# AltitudeHeadingReminder.net
KiCad netlist of a schematic drawn in EasyEDA
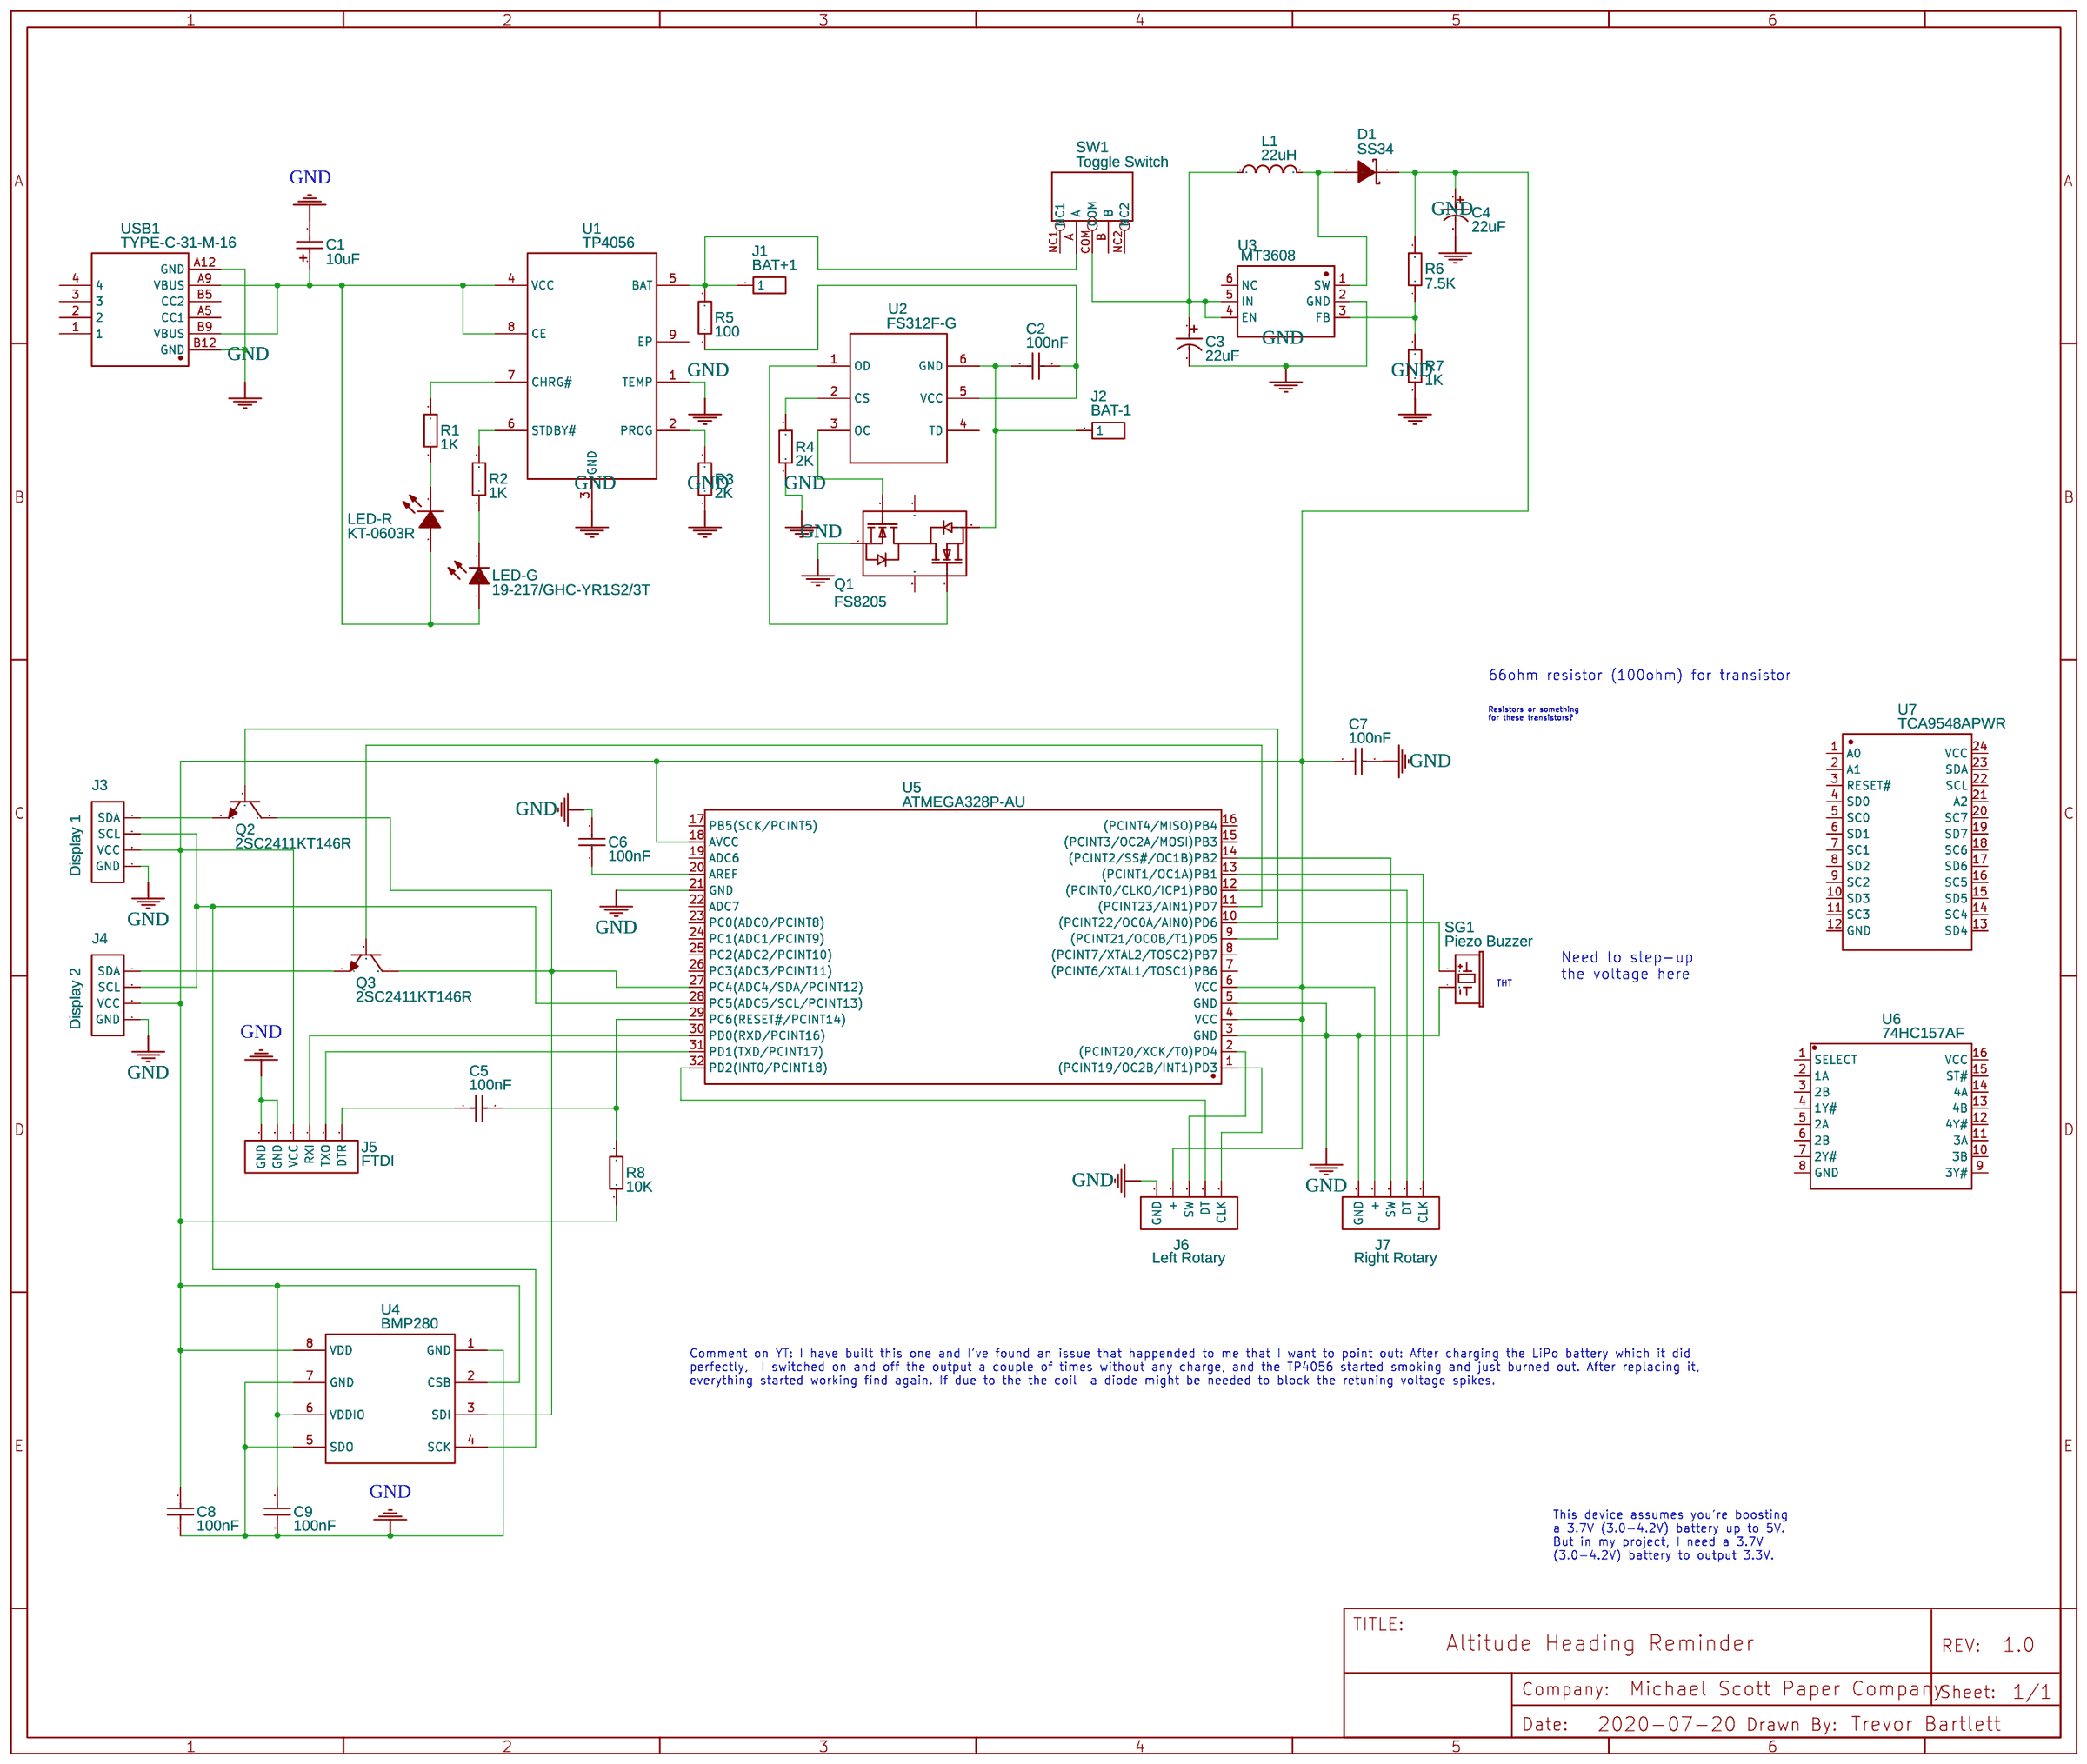
[diagram p0: schematic sheet]

(export (version "E")
  (design (tool "Eeschema 10.0.6"))
  (components
    (comp (ref "C1")
      (value "10uF")
      (fields
        (field (name "BOM_Manufacturer Part") "TAJA106K016RNJ")
        (field (name "BOM_Supplier Part") "C7171")
      )
      (libsource (lib "") (part "TAJA106K016RNJ"))
    )
    (comp (ref "C2")
      (value "100nF")
      (fields
        (field (name "BOM_Manufacturer Part") "CL05B104KO5NNNC")
        (field (name "BOM_Supplier Part") "C1525")
      )
      (libsource (lib "") (part "CL05B104KO5NNNC_3"))
    )
    (comp (ref "C3")
      (value "22uF")
      (fields
        (field (name "BOM_Manufacturer Part") "CA45-A-6.3V-22uF-M")
        (field (name "BOM_Supplier Part") "C140378")
      )
      (libsource (lib "") (part "CA45-A-6.3V-22uF-M"))
    )
    (comp (ref "C4")
      (value "22uF")
      (fields
        (field (name "BOM_Manufacturer Part") "CA45-A-6.3V-22uF-M")
        (field (name "BOM_Supplier Part") "C140378")
      )
      (libsource (lib "") (part "CA45-A-6.3V-22uF-M"))
    )
    (comp (ref "C5")
      (value "100nF")
      (fields
        (field (name "BOM_Manufacturer Part") "CL05B104KO5NNNC")
        (field (name "BOM_Supplier Part") "C1525")
      )
      (libsource (lib "") (part "CL05B104KO5NNNC_3"))
    )
    (comp (ref "C6")
      (value "100nF")
      (fields
        (field (name "BOM_Manufacturer Part") "CL05B104KO5NNNC")
        (field (name "BOM_Supplier Part") "C1525")
      )
      (libsource (lib "") (part "CL05B104KO5NNNC_1"))
    )
    (comp (ref "C7")
      (value "100nF")
      (fields
        (field (name "BOM_Manufacturer Part") "CL05B104KO5NNNC")
        (field (name "BOM_Supplier Part") "C1525")
      )
      (libsource (lib "") (part "CL05B104KO5NNNC_2"))
    )
    (comp (ref "C8")
      (value "100nF")
      (fields
        (field (name "BOM_Manufacturer Part") "CL05B104KO5NNNC")
        (field (name "BOM_Supplier Part") "C1525")
      )
      (libsource (lib "") (part "CL05B104KO5NNNC"))
    )
    (comp (ref "C9")
      (value "100nF")
      (fields
        (field (name "BOM_Manufacturer Part") "CL05B104KO5NNNC")
        (field (name "BOM_Supplier Part") "C1525")
      )
      (libsource (lib "") (part "CL05B104KO5NNNC"))
    )
    (comp (ref "D1")
      (value "SS34")
      (fields (field (name "BOM_Supplier Part") "C8678"))
      (libsource (lib "") (part "Unknown_830_-1235"))
    )
    (comp (ref "J1")
      (value "BAT+1")
      (fields (field (name "BOM_Supplier Part") "C81276"))
      (libsource (lib "") (part "HDR-M-2.54_1x1"))
    )
    (comp (ref "J2")
      (value "BAT-1")
      (fields (field (name "BOM_Supplier Part") "C81276"))
      (libsource (lib "") (part "HDR-M-2.54_1x1"))
    )
    (comp (ref "J3")
      (value "Display 1")
      (fields (field (name "BOM_Supplier Part") "C124378"))
      (libsource (lib "") (part "HDR-M-2.54_1x4"))
    )
    (comp (ref "J4")
      (value "Display 2")
      (fields (field (name "BOM_Supplier Part") "C124378"))
      (libsource (lib "") (part "HDR-M-2.54_1x4"))
    )
    (comp (ref "J5")
      (value "FTDI")
      (fields (field (name "BOM_Supplier Part") "C190819"))
      (libsource (lib "") (part "HDR-M-2.54_1x6"))
    )
    (comp (ref "J6")
      (value "Left Rotary")
      (fields (field (name "BOM_Supplier Part") "C358687"))
      (libsource (lib "") (part "HDR-M-2.54_1x5"))
    )
    (comp (ref "J7")
      (value "Right Rotary")
      (fields (field (name "BOM_Supplier Part") "C358687"))
      (libsource (lib "") (part "HDR-M-2.54_1x5"))
    )
    (comp (ref "L1")
      (value "22uH")
      (fields
        (field (name "BOM_Manufacturer Part") "SDFL2012T220KTF")
        (field (name "BOM_Supplier Part") "C32375")
      )
      (libsource (lib "") (part "SDFL2012T220KTF"))
    )
    (comp (ref "LED-G")
      (value "19-217/GHC-YR1S2/3T")
      (fields (field (name "BOM_Supplier Part") "C72043"))
      (libsource (lib "") (part "19-217/GHC-YR1S2/3T"))
    )
    (comp (ref "LED-R")
      (value "KT-0603R")
      (fields (field (name "BOM_Supplier Part") "C2286"))
      (libsource (lib "") (part "KT-0603R"))
    )
    (comp (ref "Q1")
      (value "FS8205")
      (fields (field (name "BOM_Supplier Part") "C32254"))
      (libsource (lib "") (part "Unknown_550_-1005"))
    )
    (comp (ref "Q2")
      (value "2SC2411KT146R")
      (fields (field (name "BOM_Supplier Part") "C122622"))
      (libsource (lib "") (part "2SC2411KT146R"))
    )
    (comp (ref "Q3")
      (value "2SC2411KT146R")
      (fields (field (name "BOM_Supplier Part") "C122622"))
      (libsource (lib "") (part "2SC2411KT146R"))
    )
    (comp (ref "R1")
      (value "1K")
      (fields
        (field (name "BOM_Manufacturer Part") "0402WGF1001TCE")
        (field (name "BOM_Supplier Part") "C11702")
      )
      (libsource (lib "") (part "0402WGF1001TCE"))
    )
    (comp (ref "R2")
      (value "1K")
      (fields
        (field (name "BOM_Manufacturer Part") "0402WGF1001TCE")
        (field (name "BOM_Supplier Part") "C11702")
      )
      (libsource (lib "") (part "0402WGF1001TCE"))
    )
    (comp (ref "R3")
      (value "2K")
      (fields
        (field (name "BOM_Manufacturer Part") "0402WGF2001TCE")
        (field (name "BOM_Supplier Part") "C4109")
      )
      (libsource (lib "") (part "0402WGF2001TCE"))
    )
    (comp (ref "R4")
      (value "2K")
      (fields
        (field (name "BOM_Manufacturer Part") "0402WGF2001TCE")
        (field (name "BOM_Supplier Part") "C4109")
      )
      (libsource (lib "") (part "0402WGF2001TCE"))
    )
    (comp (ref "R5")
      (value "100")
      (fields
        (field (name "BOM_Manufacturer Part") "1206W4F1000T5E")
        (field (name "BOM_Supplier Part") "C17901")
      )
      (libsource (lib "") (part "1206W4F1000T5E"))
    )
    (comp (ref "R6")
      (value "7.5K")
      (fields
        (field (name "BOM_Manufacturer Part") "AECR2010F7K50K9")
        (field (name "BOM_Supplier Part") "C351751")
      )
      (libsource (lib "") (part "AECR2010F7K50K9"))
    )
    (comp (ref "R7")
      (value "1K")
      (fields
        (field (name "BOM_Manufacturer Part") "0402WGF1001TCE")
        (field (name "BOM_Supplier Part") "C11702")
      )
      (libsource (lib "") (part "0402WGF1001TCE"))
    )
    (comp (ref "R8")
      (value "10K")
      (fields
        (field (name "BOM_Manufacturer Part") "1206W4F1002T5E")
        (field (name "BOM_Supplier Part") "C17902")
      )
      (libsource (lib "") (part "1206W4F1002T5E"))
    )
    (comp (ref "SG1") (value "Piezo Buzzer") (libsource (lib "") (part "Piezo Buzzer")))
    (comp (ref "SW1")
      (value "Toggle Switch")
      (fields (field (name "BOM_Manufacturer Part") "3P-2.0-90D-REINFORCE;"))
      (libsource (lib "") (part "Unknown_660_-1225"))
    )
    (comp (ref "U1")
      (value "TP4056")
      (fields (field (name "BOM_Supplier Part") "C16581"))
      (libsource (lib "") (part "TP4056"))
    )
    (comp (ref "U2")
      (value "FS312F-G")
      (fields (field (name "BOM_Manufacturer Part") "DW01+G") (field (name "BOM_Supplier Part") "C14213"))
      (libsource (lib "") (part "Unknown_510_-1135"))
    )
    (comp (ref "U3")
      (value "MT3608")
      (fields (field (name "BOM_Supplier Part") "C84817"))
      (libsource (lib "") (part "Unknown_790_-1175"))
    )
    (comp (ref "U4")
      (value "BMP280")
      (fields (field (name "BOM_Supplier Part") "C83291"))
      (libsource (lib "") (part "BMP280"))
    )
    (comp (ref "U5")
      (value "ATMEGA328P-AU")
      (fields (field (name "BOM_Supplier Part") "C14877"))
      (libsource (lib "") (part "ATMEGA328P-AU"))
    )
    (comp (ref "U6")
      (value "74HC157AF")
      (fields (field (name "BOM_Supplier Part") "C8166"))
      (libsource (lib "") (part "74HC157AF"))
    )
    (comp (ref "U7")
      (value "TCA9548APWR")
      (fields (field (name "BOM_Supplier Part") "C130026"))
      (libsource (lib "") (part "TCA9548APWR"))
    )
    (comp (ref "USB1")
      (value "TYPE-C-31-M-16")
      (fields (field (name "BOM_Supplier Part") "C283541"))
      (libsource (lib "") (part "TYPE-C-31-M-16"))
    )
  )
  (nets
    (net (code "1") (name "GND") (class "Default")
      (node (ref "C1") (pin "2") (pinfunction "2_2") (pintype "input"))
      (node (ref "C3") (pin "2") (pinfunction "2_2") (pintype "input"))
      (node (ref "C4") (pin "2") (pinfunction "2_2") (pintype "input"))
      (node (ref "C6") (pin "1") (pinfunction "1_1") (pintype "input"))
      (node (ref "C7") (pin "2") (pinfunction "2_2") (pintype "input"))
      (node (ref "C8") (pin "1") (pinfunction "1_1") (pintype "input"))
      (node (ref "C9") (pin "1") (pinfunction "1_1") (pintype "input"))
      (node (ref "J3") (pin "1") (pinfunction "GND_1") (pintype "unspecified"))
      (node (ref "J4") (pin "1") (pinfunction "GND_1") (pintype "unspecified"))
      (node (ref "J5") (pin "5") (pinfunction "GND_5") (pintype "unspecified"))
      (node (ref "J5") (pin "6") (pinfunction "GND_6") (pintype "unspecified"))
      (node (ref "J6") (pin "5") (pinfunction "GND_5") (pintype "unspecified"))
      (node (ref "J7") (pin "5") (pinfunction "GND_5") (pintype "unspecified"))
      (node (ref "Q1") (pin "1") (pinfunction "S1_1") (pintype "unspecified"))
      (node (ref "R3") (pin "1") (pinfunction "1_1") (pintype "input"))
      (node (ref "R4") (pin "1") (pinfunction "1_1") (pintype "input"))
      (node (ref "R7") (pin "1") (pinfunction "1_1") (pintype "input"))
      (node (ref "SG1") (pin "-") (pinfunction "2_-") (pintype "unspecified"))
      (node (ref "U1") (pin "1") (pinfunction "TEMP_1") (pintype "unspecified"))
      (node (ref "U1") (pin "3") (pinfunction "GND_3") (pintype "unspecified"))
      (node (ref "U3") (pin "2") (pinfunction "GND_2") (pintype "unspecified"))
      (node (ref "U4") (pin "1") (pinfunction "GND_1") (pintype "unspecified"))
      (node (ref "U4") (pin "5") (pinfunction "SDO_5") (pintype "unspecified"))
      (node (ref "U4") (pin "7") (pinfunction "GND_7") (pintype "unspecified"))
      (node (ref "U5") (pin "21") (pinfunction "GND_21") (pintype "unspecified"))
      (node (ref "U5") (pin "3") (pinfunction "GND_3") (pintype "unspecified"))
      (node (ref "U5") (pin "5") (pinfunction "GND_5") (pintype "unspecified"))
      (node (ref "USB1") (pin "A12") (pinfunction "GND_A12") (pintype "unspecified"))
      (node (ref "USB1") (pin "B12") (pinfunction "GND_B12") (pintype "unspecified"))
    )
    (net (code "2") (name "Net-(D1-A)") (class "Default")
      (node (ref "D1") (pin "1") (pinfunction "A_1") (pintype "unspecified"))
      (node (ref "L1") (pin "2") (pinfunction "2_2") (pintype "unspecified"))
      (node (ref "U3") (pin "1") (pinfunction "SW_1") (pintype "unspecified"))
    )
    (net (code "3") (name "Net-(D1-K)") (class "Default")
      (node (ref "C4") (pin "1") (pinfunction "1_1") (pintype "input"))
      (node (ref "C7") (pin "1") (pinfunction "1_1") (pintype "input"))
      (node (ref "C8") (pin "2") (pinfunction "2_2") (pintype "input"))
      (node (ref "C9") (pin "2") (pinfunction "2_2") (pintype "input"))
      (node (ref "D1") (pin "2") (pinfunction "K_2") (pintype "unspecified"))
      (node (ref "J3") (pin "2") (pinfunction "VCC_2") (pintype "unspecified"))
      (node (ref "J4") (pin "2") (pinfunction "VCC_2") (pintype "unspecified"))
      (node (ref "J5") (pin "4") (pinfunction "VCC_4") (pintype "passive"))
      (node (ref "J6") (pin "4") (pinfunction "+_4") (pintype "unspecified"))
      (node (ref "J7") (pin "4") (pinfunction "+_4") (pintype "unspecified"))
      (node (ref "R6") (pin "2") (pinfunction "2_2") (pintype "unspecified"))
      (node (ref "R8") (pin "1") (pinfunction "1_1") (pintype "input"))
      (node (ref "U4") (pin "2") (pinfunction "CSB_2") (pintype "unspecified"))
      (node (ref "U4") (pin "6") (pinfunction "VDDIO_6") (pintype "unspecified"))
      (node (ref "U4") (pin "8") (pinfunction "VDD_8") (pintype "unspecified"))
      (node (ref "U5") (pin "18") (pinfunction "AVCC_18") (pintype "unspecified"))
      (node (ref "U5") (pin "4") (pinfunction "VCC_4") (pintype "unspecified"))
      (node (ref "U5") (pin "6") (pinfunction "VCC_6") (pintype "unspecified"))
    )
    (net (code "4") (name "Net-(J3-SCL)") (class "Default")
      (node (ref "J3") (pin "3") (pinfunction "SCL_3") (pintype "unspecified"))
      (node (ref "J4") (pin "3") (pinfunction "SCL_3") (pintype "unspecified"))
      (node (ref "U4") (pin "4") (pinfunction "SCK_4") (pintype "unspecified"))
      (node (ref "U5") (pin "28") (pinfunction "PC5(ADC5/SCL/PCINT13)_28") (pintype "unspecified"))
    )
    (net (code "5") (name "Net-(J3-SDA)") (class "Default")
      (node (ref "J3") (pin "4") (pinfunction "SDA_4") (pintype "unspecified"))
      (node (ref "Q2") (pin "1") (pinfunction "E_1") (pintype "unspecified"))
    )
    (net (code "6") (name "Net-(J4-SDA)") (class "Default")
      (node (ref "J4") (pin "4") (pinfunction "SDA_4") (pintype "unspecified"))
      (node (ref "Q3") (pin "1") (pinfunction "E_1") (pintype "unspecified"))
    )
    (net (code "7") (name "Net-(J5-DTR)") (class "Default")
      (node (ref "C5") (pin "2") (pinfunction "2_2") (pintype "input"))
      (node (ref "J5") (pin "1") (pinfunction "DTR_1") (pintype "unspecified"))
    )
    (net (code "8") (name "Net-(J5-RXI)") (class "Default")
      (node (ref "J5") (pin "3") (pinfunction "RXI_3") (pintype "unspecified"))
      (node (ref "U5") (pin "30") (pinfunction "PD0(RXD/PCINT16)_30") (pintype "unspecified"))
    )
    (net (code "9") (name "Net-(J5-TXO)") (class "Default")
      (node (ref "J5") (pin "2") (pinfunction "TXO_2") (pintype "unspecified"))
      (node (ref "U5") (pin "31") (pinfunction "PD1(TXD/PCINT17)_31") (pintype "unspecified"))
    )
    (net (code "10") (name "Net-(J6-CLK)") (class "Default")
      (node (ref "J6") (pin "1") (pinfunction "CLK_1") (pintype "unspecified"))
      (node (ref "U5") (pin "1") (pinfunction "(PCINT19/OC2B/INT1)PD3_1") (pintype "unspecified"))
    )
    (net (code "11") (name "Net-(J6-DT)") (class "Default")
      (node (ref "J6") (pin "2") (pinfunction "DT_2") (pintype "unspecified"))
      (node (ref "U5") (pin "32") (pinfunction "PD2(INT0/PCINT18)_32") (pintype "unspecified"))
    )
    (net (code "12") (name "Net-(J6-SW)") (class "Default")
      (node (ref "J6") (pin "3") (pinfunction "SW_3") (pintype "unspecified"))
      (node (ref "U5") (pin "2") (pinfunction "(PCINT20/XCK/T0)PD4_2") (pintype "unspecified"))
    )
    (net (code "13") (name "Net-(J7-CLK)") (class "Default")
      (node (ref "J7") (pin "1") (pinfunction "CLK_1") (pintype "unspecified"))
      (node (ref "U5") (pin "13") (pinfunction "(PCINT1/OC1A)PB1_13") (pintype "unspecified"))
    )
    (net (code "14") (name "Net-(J7-DT)") (class "Default")
      (node (ref "J7") (pin "2") (pinfunction "DT_2") (pintype "unspecified"))
      (node (ref "U5") (pin "12") (pinfunction "(PCINT0/CLKO/ICP1)PB0_12") (pintype "unspecified"))
    )
    (net (code "15") (name "Net-(J7-SW)") (class "Default")
      (node (ref "J7") (pin "3") (pinfunction "SW_3") (pintype "unspecified"))
      (node (ref "U5") (pin "14") (pinfunction "(PCINT2/SS#/OC1B)PB2_14") (pintype "unspecified"))
    )
    (net (code "16") (name "Net-(LED-G-A)") (class "Default")
      (node (ref "C1") (pin "1") (pinfunction "1_1") (pintype "input"))
      (node (ref "LED-G") (pin "1") (pinfunction "A_1") (pintype "input"))
      (node (ref "LED-R") (pin "1") (pinfunction "A_1") (pintype "unspecified"))
      (node (ref "U1") (pin "4") (pinfunction "VCC_4") (pintype "unspecified"))
      (node (ref "U1") (pin "8") (pinfunction "CE_8") (pintype "unspecified"))
      (node (ref "USB1") (pin "A9") (pinfunction "VBUS_A9") (pintype "unspecified"))
      (node (ref "USB1") (pin "B9") (pinfunction "VBUS_B9") (pintype "unspecified"))
    )
    (net (code "17") (name "Net-(LED-G-C)") (class "Default")
      (node (ref "LED-G") (pin "2") (pinfunction "C_2") (pintype "input"))
      (node (ref "R2") (pin "1") (pinfunction "1_1") (pintype "input"))
    )
    (net (code "18") (name "Net-(LED-R-K)") (class "Default")
      (node (ref "LED-R") (pin "2") (pinfunction "K_2") (pintype "unspecified"))
      (node (ref "R1") (pin "1") (pinfunction "1_1") (pintype "input"))
    )
    (net (code "19") (name "Net-(Q1-G1)") (class "Default")
      (node (ref "Q1") (pin "6") (pinfunction "G1_6") (pintype "unspecified"))
      (node (ref "U2") (pin "3") (pinfunction "OC_3") (pintype "unspecified"))
    )
    (net (code "20") (name "Net-(Q1-G2)") (class "Default")
      (node (ref "Q1") (pin "4") (pinfunction "G2_4") (pintype "unspecified"))
      (node (ref "U2") (pin "1") (pinfunction "OD_1") (pintype "unspecified"))
    )
    (net (code "21") (name "Net-(Q1-S2)") (class "Default")
      (node (ref "C2") (pin "2") (pinfunction "2_2") (pintype "input"))
      (node (ref "J2") (pin "1") (pinfunction "1_1") (pintype "input"))
      (node (ref "Q1") (pin "3") (pinfunction "S2_3") (pintype "unspecified"))
      (node (ref "U2") (pin "6") (pinfunction "GND_6") (pintype "unspecified"))
    )
    (net (code "22") (name "Net-(Q2-B)") (class "Default")
      (node (ref "Q2") (pin "2") (pinfunction "B_2") (pintype "unspecified"))
      (node (ref "U5") (pin "9") (pinfunction "(PCINT21/OC0B/T1)PD5_9") (pintype "unspecified"))
    )
    (net (code "23") (name "Net-(Q2-C)") (class "Default")
      (node (ref "Q2") (pin "3") (pinfunction "C_3") (pintype "unspecified"))
      (node (ref "Q3") (pin "3") (pinfunction "C_3") (pintype "unspecified"))
      (node (ref "U4") (pin "3") (pinfunction "SDI_3") (pintype "unspecified"))
      (node (ref "U5") (pin "27") (pinfunction "PC4(ADC4/SDA/PCINT12)_27") (pintype "unspecified"))
    )
    (net (code "24") (name "Net-(Q3-B)") (class "Default")
      (node (ref "Q3") (pin "2") (pinfunction "B_2") (pintype "unspecified"))
      (node (ref "U5") (pin "11") (pinfunction "(PCINT23/AIN1)PD7_11") (pintype "unspecified"))
    )
    (net (code "25") (name "Net-(SG1-1)") (class "Default")
      (node (ref "SG1") (pin "+") (pinfunction "1_+") (pintype "unspecified"))
      (node (ref "U5") (pin "10") (pinfunction "(PCINT22/OC0A/AIN0)PD6_10") (pintype "unspecified"))
    )
    (net (code "26") (name "Net-(U1-BAT)") (class "Default")
      (node (ref "J1") (pin "1") (pinfunction "1_1") (pintype "input"))
      (node (ref "R5") (pin "2") (pinfunction "2_2") (pintype "input"))
      (node (ref "SW1") (pin "A") (pinfunction "A_A") (pintype "unspecified"))
      (node (ref "U1") (pin "5") (pinfunction "BAT_5") (pintype "unspecified"))
    )
    (net (code "27") (name "Net-(U1-CHRG#)") (class "Default")
      (node (ref "R1") (pin "2") (pinfunction "2_2") (pintype "input"))
      (node (ref "U1") (pin "7") (pinfunction "CHRG#_7") (pintype "unspecified"))
    )
    (net (code "28") (name "Net-(U1-PROG)") (class "Default")
      (node (ref "R3") (pin "2") (pinfunction "2_2") (pintype "input"))
      (node (ref "U1") (pin "2") (pinfunction "PROG_2") (pintype "unspecified"))
    )
    (net (code "29") (name "Net-(U1-STDBY#)") (class "Default")
      (node (ref "R2") (pin "2") (pinfunction "2_2") (pintype "input"))
      (node (ref "U1") (pin "6") (pinfunction "STDBY#_6") (pintype "unspecified"))
    )
    (net (code "30") (name "Net-(U2-CS)") (class "Default")
      (node (ref "R4") (pin "2") (pinfunction "2_2") (pintype "input"))
      (node (ref "U2") (pin "2") (pinfunction "CS_2") (pintype "unspecified"))
    )
    (net (code "31") (name "Net-(U2-VCC)") (class "Default")
      (node (ref "C2") (pin "1") (pinfunction "1_1") (pintype "input"))
      (node (ref "R5") (pin "1") (pinfunction "1_1") (pintype "input"))
      (node (ref "U2") (pin "5") (pinfunction "VCC_5") (pintype "unspecified"))
    )
    (net (code "32") (name "Net-(U3-EN)") (class "Default")
      (node (ref "C3") (pin "1") (pinfunction "1_1") (pintype "input"))
      (node (ref "L1") (pin "1") (pinfunction "1_1") (pintype "unspecified"))
      (node (ref "SW1") (pin "COM") (pinfunction "COM_COM") (pintype "unspecified"))
      (node (ref "U3") (pin "4") (pinfunction "EN_4") (pintype "unspecified"))
      (node (ref "U3") (pin "5") (pinfunction "IN_5") (pintype "unspecified"))
    )
    (net (code "33") (name "Net-(U3-FB)") (class "Default")
      (node (ref "R6") (pin "1") (pinfunction "1_1") (pintype "unspecified"))
      (node (ref "R7") (pin "2") (pinfunction "2_2") (pintype "input"))
      (node (ref "U3") (pin "3") (pinfunction "FB_3") (pintype "unspecified"))
    )
    (net (code "34") (name "Net-(U5-AREF)") (class "Default")
      (node (ref "C6") (pin "2") (pinfunction "2_2") (pintype "input"))
      (node (ref "U5") (pin "20") (pinfunction "AREF_20") (pintype "unspecified"))
    )
    (net (code "35") (name "Net-(U5-PC6(RESET#{slash}PCINT14))") (class "Default")
      (node (ref "C5") (pin "1") (pinfunction "1_1") (pintype "input"))
      (node (ref "R8") (pin "2") (pinfunction "2_2") (pintype "input"))
      (node (ref "U5") (pin "29") (pinfunction "PC6(RESET#/PCINT14)_29") (pintype "unspecified"))
    )
    (net (code "36") (name "unconnected-(Q1-D12-Pad2)") (class "Default")
      (node (ref "Q1") (pin "2") (pinfunction "D12_2") (pintype "unspecified"))
    )
    (net (code "37") (name "unconnected-(Q1-D12-Pad5)") (class "Default")
      (node (ref "Q1") (pin "5") (pinfunction "D12_5") (pintype "unspecified"))
    )
    (net (code "38") (name "unconnected-(SW1-PadB)") (class "Default")
      (node (ref "SW1") (pin "B") (pinfunction "B_B") (pintype "unspecified"))
    )
    (net (code "39") (name "unconnected-(SW1-PadNC1)") (class "Default")
      (node (ref "SW1") (pin "NC1") (pinfunction "NC1_NC1") (pintype "unspecified"))
    )
    (net (code "40") (name "unconnected-(SW1-PadNC2)") (class "Default")
      (node (ref "SW1") (pin "NC2") (pinfunction "NC2_NC2") (pintype "unspecified"))
    )
    (net (code "41") (name "unconnected-(U1-EP-Pad9)") (class "Default")
      (node (ref "U1") (pin "9") (pinfunction "EP_9") (pintype "unspecified"))
    )
    (net (code "42") (name "unconnected-(U2-TD-Pad4)") (class "Default")
      (node (ref "U2") (pin "4") (pinfunction "TD_4") (pintype "unspecified"))
    )
    (net (code "43") (name "unconnected-(U3-NC-Pad6)") (class "Default")
      (node (ref "U3") (pin "6") (pinfunction "NC_6") (pintype "unspecified"))
    )
    (net (code "44") (name "unconnected-(U5-(PCINT3{slash}OC2A{slash}MOSI)PB3-Pad15)") (class "Default")
      (node (ref "U5") (pin "15") (pinfunction "(PCINT3/OC2A/MOSI)PB3_15") (pintype "unspecified"))
    )
    (net (code "45") (name "unconnected-(U5-(PCINT4{slash}MISO)PB4-Pad16)") (class "Default")
      (node (ref "U5") (pin "16") (pinfunction "(PCINT4/MISO)PB4_16") (pintype "unspecified"))
    )
    (net (code "46") (name "unconnected-(U5-(PCINT6{slash}XTAL1{slash}TOSC1)PB6-Pad7)") (class "Default")
      (node (ref "U5") (pin "7") (pinfunction "(PCINT6/XTAL1/TOSC1)PB6_7") (pintype "unspecified"))
    )
    (net (code "47") (name "unconnected-(U5-(PCINT7{slash}XTAL2{slash}TOSC2)PB7-Pad8)") (class "Default")
      (node (ref "U5") (pin "8") (pinfunction "(PCINT7/XTAL2/TOSC2)PB7_8") (pintype "unspecified"))
    )
    (net (code "48") (name "unconnected-(U5-ADC6-Pad19)") (class "Default")
      (node (ref "U5") (pin "19") (pinfunction "ADC6_19") (pintype "unspecified"))
    )
    (net (code "49") (name "unconnected-(U5-ADC7-Pad22)") (class "Default")
      (node (ref "U5") (pin "22") (pinfunction "ADC7_22") (pintype "unspecified"))
    )
    (net (code "50") (name "unconnected-(U5-PB5(SCK{slash}PCINT5)-Pad17)") (class "Default")
      (node (ref "U5") (pin "17") (pinfunction "PB5(SCK/PCINT5)_17") (pintype "unspecified"))
    )
    (net (code "51") (name "unconnected-(U5-PC0(ADC0{slash}PCINT8)-Pad23)") (class "Default")
      (node (ref "U5") (pin "23") (pinfunction "PC0(ADC0/PCINT8)_23") (pintype "unspecified"))
    )
    (net (code "52") (name "unconnected-(U5-PC1(ADC1{slash}PCINT9)-Pad24)") (class "Default")
      (node (ref "U5") (pin "24") (pinfunction "PC1(ADC1/PCINT9)_24") (pintype "unspecified"))
    )
    (net (code "53") (name "unconnected-(U5-PC2(ADC2{slash}PCINT10)-Pad25)") (class "Default")
      (node (ref "U5") (pin "25") (pinfunction "PC2(ADC2/PCINT10)_25") (pintype "unspecified"))
    )
    (net (code "54") (name "unconnected-(U5-PC3(ADC3{slash}PCINT11)-Pad26)") (class "Default")
      (node (ref "U5") (pin "26") (pinfunction "PC3(ADC3/PCINT11)_26") (pintype "unspecified"))
    )
    (net (code "55") (name "unconnected-(U6-1A-Pad2)") (class "Default")
      (node (ref "U6") (pin "2") (pinfunction "1A_2") (pintype "unspecified"))
    )
    (net (code "56") (name "unconnected-(U6-1Y#-Pad4)") (class "Default")
      (node (ref "U6") (pin "4") (pinfunction "1Y#_4") (pintype "unspecified"))
    )
    (net (code "57") (name "unconnected-(U6-2A-Pad5)") (class "Default")
      (node (ref "U6") (pin "5") (pinfunction "2A_5") (pintype "unspecified"))
    )
    (net (code "58") (name "unconnected-(U6-2B-Pad3)") (class "Default")
      (node (ref "U6") (pin "3") (pinfunction "2B_3") (pintype "unspecified"))
    )
    (net (code "59") (name "unconnected-(U6-2B-Pad6)") (class "Default")
      (node (ref "U6") (pin "6") (pinfunction "2B_6") (pintype "unspecified"))
    )
    (net (code "60") (name "unconnected-(U6-2Y#-Pad7)") (class "Default")
      (node (ref "U6") (pin "7") (pinfunction "2Y#_7") (pintype "unspecified"))
    )
    (net (code "61") (name "unconnected-(U6-3A-Pad11)") (class "Default")
      (node (ref "U6") (pin "11") (pinfunction "3A_11") (pintype "unspecified"))
    )
    (net (code "62") (name "unconnected-(U6-3B-Pad10)") (class "Default")
      (node (ref "U6") (pin "10") (pinfunction "3B_10") (pintype "unspecified"))
    )
    (net (code "63") (name "unconnected-(U6-3Y#-Pad9)") (class "Default")
      (node (ref "U6") (pin "9") (pinfunction "3Y#_9") (pintype "unspecified"))
    )
    (net (code "64") (name "unconnected-(U6-4A-Pad14)") (class "Default")
      (node (ref "U6") (pin "14") (pinfunction "4A_14") (pintype "unspecified"))
    )
    (net (code "65") (name "unconnected-(U6-4B-Pad13)") (class "Default")
      (node (ref "U6") (pin "13") (pinfunction "4B_13") (pintype "unspecified"))
    )
    (net (code "66") (name "unconnected-(U6-4Y#-Pad12)") (class "Default")
      (node (ref "U6") (pin "12") (pinfunction "4Y#_12") (pintype "unspecified"))
    )
    (net (code "67") (name "unconnected-(U6-GND-Pad8)") (class "Default")
      (node (ref "U6") (pin "8") (pinfunction "GND_8") (pintype "unspecified"))
    )
    (net (code "68") (name "unconnected-(U6-SELECT-Pad1)") (class "Default")
      (node (ref "U6") (pin "1") (pinfunction "SELECT_1") (pintype "unspecified"))
    )
    (net (code "69") (name "unconnected-(U6-ST#-Pad15)") (class "Default")
      (node (ref "U6") (pin "15") (pinfunction "ST#_15") (pintype "unspecified"))
    )
    (net (code "70") (name "unconnected-(U6-VCC-Pad16)") (class "Default")
      (node (ref "U6") (pin "16") (pinfunction "VCC_16") (pintype "unspecified"))
    )
    (net (code "71") (name "unconnected-(U7-A0-Pad1)") (class "Default")
      (node (ref "U7") (pin "1") (pinfunction "A0_1") (pintype "unspecified"))
    )
    (net (code "72") (name "unconnected-(U7-A1-Pad2)") (class "Default")
      (node (ref "U7") (pin "2") (pinfunction "A1_2") (pintype "unspecified"))
    )
    (net (code "73") (name "unconnected-(U7-A2-Pad21)") (class "Default")
      (node (ref "U7") (pin "21") (pinfunction "A2_21") (pintype "unspecified"))
    )
    (net (code "74") (name "unconnected-(U7-GND-Pad12)") (class "Default")
      (node (ref "U7") (pin "12") (pinfunction "GND_12") (pintype "unspecified"))
    )
    (net (code "75") (name "unconnected-(U7-RESET#-Pad3)") (class "Default")
      (node (ref "U7") (pin "3") (pinfunction "RESET#_3") (pintype "unspecified"))
    )
    (net (code "76") (name "unconnected-(U7-SC0-Pad5)") (class "Default")
      (node (ref "U7") (pin "5") (pinfunction "SC0_5") (pintype "unspecified"))
    )
    (net (code "77") (name "unconnected-(U7-SC1-Pad7)") (class "Default")
      (node (ref "U7") (pin "7") (pinfunction "SC1_7") (pintype "unspecified"))
    )
    (net (code "78") (name "unconnected-(U7-SC2-Pad9)") (class "Default")
      (node (ref "U7") (pin "9") (pinfunction "SC2_9") (pintype "unspecified"))
    )
    (net (code "79") (name "unconnected-(U7-SC3-Pad11)") (class "Default")
      (node (ref "U7") (pin "11") (pinfunction "SC3_11") (pintype "unspecified"))
    )
    (net (code "80") (name "unconnected-(U7-SC4-Pad14)") (class "Default")
      (node (ref "U7") (pin "14") (pinfunction "SC4_14") (pintype "unspecified"))
    )
    (net (code "81") (name "unconnected-(U7-SC5-Pad16)") (class "Default")
      (node (ref "U7") (pin "16") (pinfunction "SC5_16") (pintype "unspecified"))
    )
    (net (code "82") (name "unconnected-(U7-SC6-Pad18)") (class "Default")
      (node (ref "U7") (pin "18") (pinfunction "SC6_18") (pintype "unspecified"))
    )
    (net (code "83") (name "unconnected-(U7-SC7-Pad20)") (class "Default")
      (node (ref "U7") (pin "20") (pinfunction "SC7_20") (pintype "unspecified"))
    )
    (net (code "84") (name "unconnected-(U7-SCL-Pad22)") (class "Default")
      (node (ref "U7") (pin "22") (pinfunction "SCL_22") (pintype "unspecified"))
    )
    (net (code "85") (name "unconnected-(U7-SD0-Pad4)") (class "Default")
      (node (ref "U7") (pin "4") (pinfunction "SD0_4") (pintype "unspecified"))
    )
    (net (code "86") (name "unconnected-(U7-SD1-Pad6)") (class "Default")
      (node (ref "U7") (pin "6") (pinfunction "SD1_6") (pintype "unspecified"))
    )
    (net (code "87") (name "unconnected-(U7-SD2-Pad8)") (class "Default")
      (node (ref "U7") (pin "8") (pinfunction "SD2_8") (pintype "unspecified"))
    )
    (net (code "88") (name "unconnected-(U7-SD3-Pad10)") (class "Default")
      (node (ref "U7") (pin "10") (pinfunction "SD3_10") (pintype "unspecified"))
    )
    (net (code "89") (name "unconnected-(U7-SD4-Pad13)") (class "Default")
      (node (ref "U7") (pin "13") (pinfunction "SD4_13") (pintype "unspecified"))
    )
    (net (code "90") (name "unconnected-(U7-SD5-Pad15)") (class "Default")
      (node (ref "U7") (pin "15") (pinfunction "SD5_15") (pintype "unspecified"))
    )
    (net (code "91") (name "unconnected-(U7-SD6-Pad17)") (class "Default")
      (node (ref "U7") (pin "17") (pinfunction "SD6_17") (pintype "unspecified"))
    )
    (net (code "92") (name "unconnected-(U7-SD7-Pad19)") (class "Default")
      (node (ref "U7") (pin "19") (pinfunction "SD7_19") (pintype "unspecified"))
    )
    (net (code "93") (name "unconnected-(U7-SDA-Pad23)") (class "Default")
      (node (ref "U7") (pin "23") (pinfunction "SDA_23") (pintype "unspecified"))
    )
    (net (code "94") (name "unconnected-(U7-VCC-Pad24)") (class "Default")
      (node (ref "U7") (pin "24") (pinfunction "VCC_24") (pintype "unspecified"))
    )
    (net (code "95") (name "unconnected-(USB1-CC1-PadA5)") (class "Default")
      (node (ref "USB1") (pin "A5") (pinfunction "CC1_A5") (pintype "unspecified"))
    )
    (net (code "96") (name "unconnected-(USB1-CC2-PadB5)") (class "Default")
      (node (ref "USB1") (pin "B5") (pinfunction "CC2_B5") (pintype "unspecified"))
    )
    (net (code "97") (name "unconnected-(USB1-Pad1)") (class "Default")
      (node (ref "USB1") (pin "1") (pinfunction "1_1") (pintype "unspecified"))
    )
    (net (code "98") (name "unconnected-(USB1-Pad2)") (class "Default")
      (node (ref "USB1") (pin "2") (pinfunction "2_2") (pintype "unspecified"))
    )
    (net (code "99") (name "unconnected-(USB1-Pad3)") (class "Default")
      (node (ref "USB1") (pin "3") (pinfunction "3_3") (pintype "unspecified"))
    )
    (net (code "100") (name "unconnected-(USB1-Pad4)") (class "Default")
      (node (ref "USB1") (pin "4") (pinfunction "4_4") (pintype "unspecified"))
    )
  )
)
